# user_interface.net
KiCad netlist of a schematic drawn in EAGLE
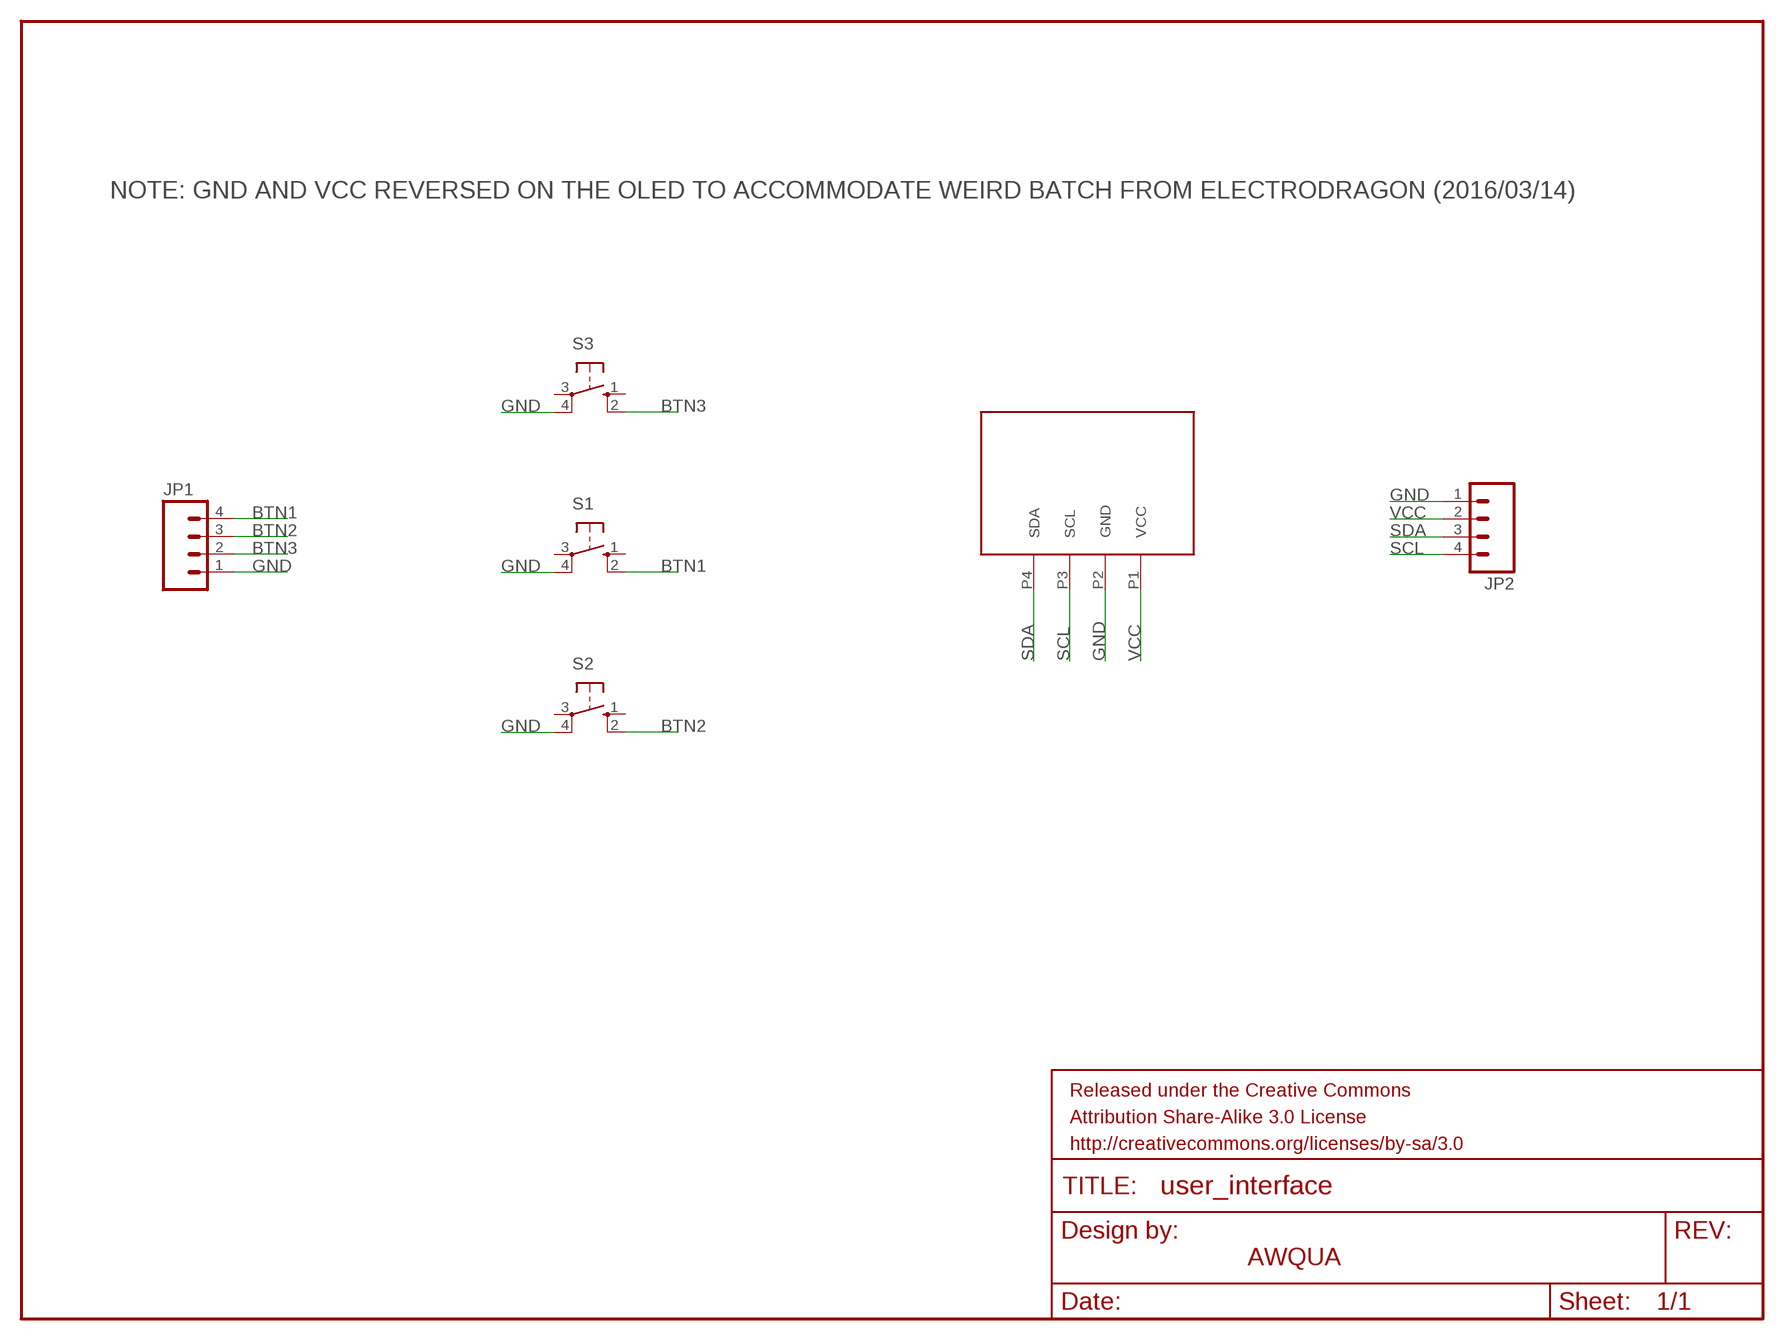
[diagram p0: schematic, sheet 1]

(export (version "E")
  (design (tool "Eeschema 10.0.6"))
  (components
    (comp (ref "FRAME1")
      (value "FRAME-LETTER")
      (footprint "eagle-import:CREATIVE_COMMONS")
      (libsource (lib "eagle-import") (part "FRAME-LETTER"))
    )
    (comp (ref "JP1")
      (value "M04PTH")
      (footprint "eagle-import:1X04")
      (libsource (lib "eagle-import") (part "M04PTH"))
    )
    (comp (ref "JP2")
      (value "M04PTH")
      (footprint "eagle-import:1X04")
      (libsource (lib "eagle-import") (part "M04PTH"))
    )
    (comp (ref "S1")
      (value "40-XX")
      (footprint "eagle-import:B3F-40XX")
      (fields (field (name "MF") "OMRON COMPONENTS USA") (field (name "MPN") "B3F-4000"))
      (libsource (lib "eagle-import") (part "40-XX"))
    )
    (comp (ref "S2")
      (value "40-XX")
      (footprint "eagle-import:B3F-40XX")
      (fields (field (name "MF") "OMRON COMPONENTS USA") (field (name "MPN") "B3F-4000"))
      (libsource (lib "eagle-import") (part "40-XX"))
    )
    (comp (ref "S3")
      (value "40-XX")
      (footprint "eagle-import:B3F-40XX")
      (fields (field (name "MF") "OMRON COMPONENTS USA") (field (name "MPN") "B3F-4000"))
      (libsource (lib "eagle-import") (part "40-XX"))
    )
    (comp (ref "U$2")
      (value "I2C-OLED-096")
      (footprint "eagle-import:I2C-OLED-096")
      (libsource (lib "eagle-import") (part "I2C-OLED-096"))
    )
  )
  (nets
    (net (code "1") (name "/BTN1") (class "Default")
      (node (ref "JP1") (pin "4") (pinfunction "4_4") (pintype "passive"))
      (node (ref "S1") (pin "2") (pinfunction "S1_2") (pintype "passive"))
    )
    (net (code "2") (name "/BTN2") (class "Default")
      (node (ref "JP1") (pin "3") (pinfunction "3_3") (pintype "passive"))
      (node (ref "S2") (pin "2") (pinfunction "S1_2") (pintype "passive"))
    )
    (net (code "3") (name "/BTN3") (class "Default")
      (node (ref "JP1") (pin "2") (pinfunction "2_2") (pintype "passive"))
      (node (ref "S3") (pin "2") (pinfunction "S1_2") (pintype "passive"))
    )
    (net (code "4") (name "/GND") (class "Default")
      (node (ref "JP1") (pin "1") (pinfunction "1_1") (pintype "passive"))
      (node (ref "JP2") (pin "1") (pinfunction "1_1") (pintype "passive"))
      (node (ref "S1") (pin "4") (pinfunction "P1_4") (pintype "passive"))
      (node (ref "S2") (pin "4") (pinfunction "P1_4") (pintype "passive"))
      (node (ref "S3") (pin "4") (pinfunction "P1_4") (pintype "passive"))
      (node (ref "U$2") (pin "P2") (pinfunction "GND_P2") (pintype "bidirectional"))
    )
    (net (code "5") (name "/SCL") (class "Default")
      (node (ref "JP2") (pin "4") (pinfunction "4_4") (pintype "passive"))
      (node (ref "U$2") (pin "P3") (pinfunction "SCL_P3") (pintype "bidirectional"))
    )
    (net (code "6") (name "/SDA") (class "Default")
      (node (ref "JP2") (pin "3") (pinfunction "3_3") (pintype "passive"))
      (node (ref "U$2") (pin "P4") (pinfunction "SDA_P4") (pintype "bidirectional"))
    )
    (net (code "7") (name "/VCC") (class "Default")
      (node (ref "JP2") (pin "2") (pinfunction "2_2") (pintype "passive"))
      (node (ref "U$2") (pin "P1") (pinfunction "VCC_P1") (pintype "bidirectional"))
    )
    (net (code "8") (name "unconnected-(S1-P-Pad3)") (class "Default")
      (node (ref "S1") (pin "3") (pinfunction "P_3") (pintype "passive"))
    )
    (net (code "9") (name "unconnected-(S1-S-Pad1)") (class "Default")
      (node (ref "S1") (pin "1") (pinfunction "S_1") (pintype "passive"))
    )
    (net (code "10") (name "unconnected-(S2-P-Pad3)") (class "Default")
      (node (ref "S2") (pin "3") (pinfunction "P_3") (pintype "passive"))
    )
    (net (code "11") (name "unconnected-(S2-S-Pad1)") (class "Default")
      (node (ref "S2") (pin "1") (pinfunction "S_1") (pintype "passive"))
    )
    (net (code "12") (name "unconnected-(S3-P-Pad3)") (class "Default")
      (node (ref "S3") (pin "3") (pinfunction "P_3") (pintype "passive"))
    )
    (net (code "13") (name "unconnected-(S3-S-Pad1)") (class "Default")
      (node (ref "S3") (pin "1") (pinfunction "S_1") (pintype "passive"))
    )
  )
)
